# main_board.net
KiCad netlist of a schematic drawn in EAGLE
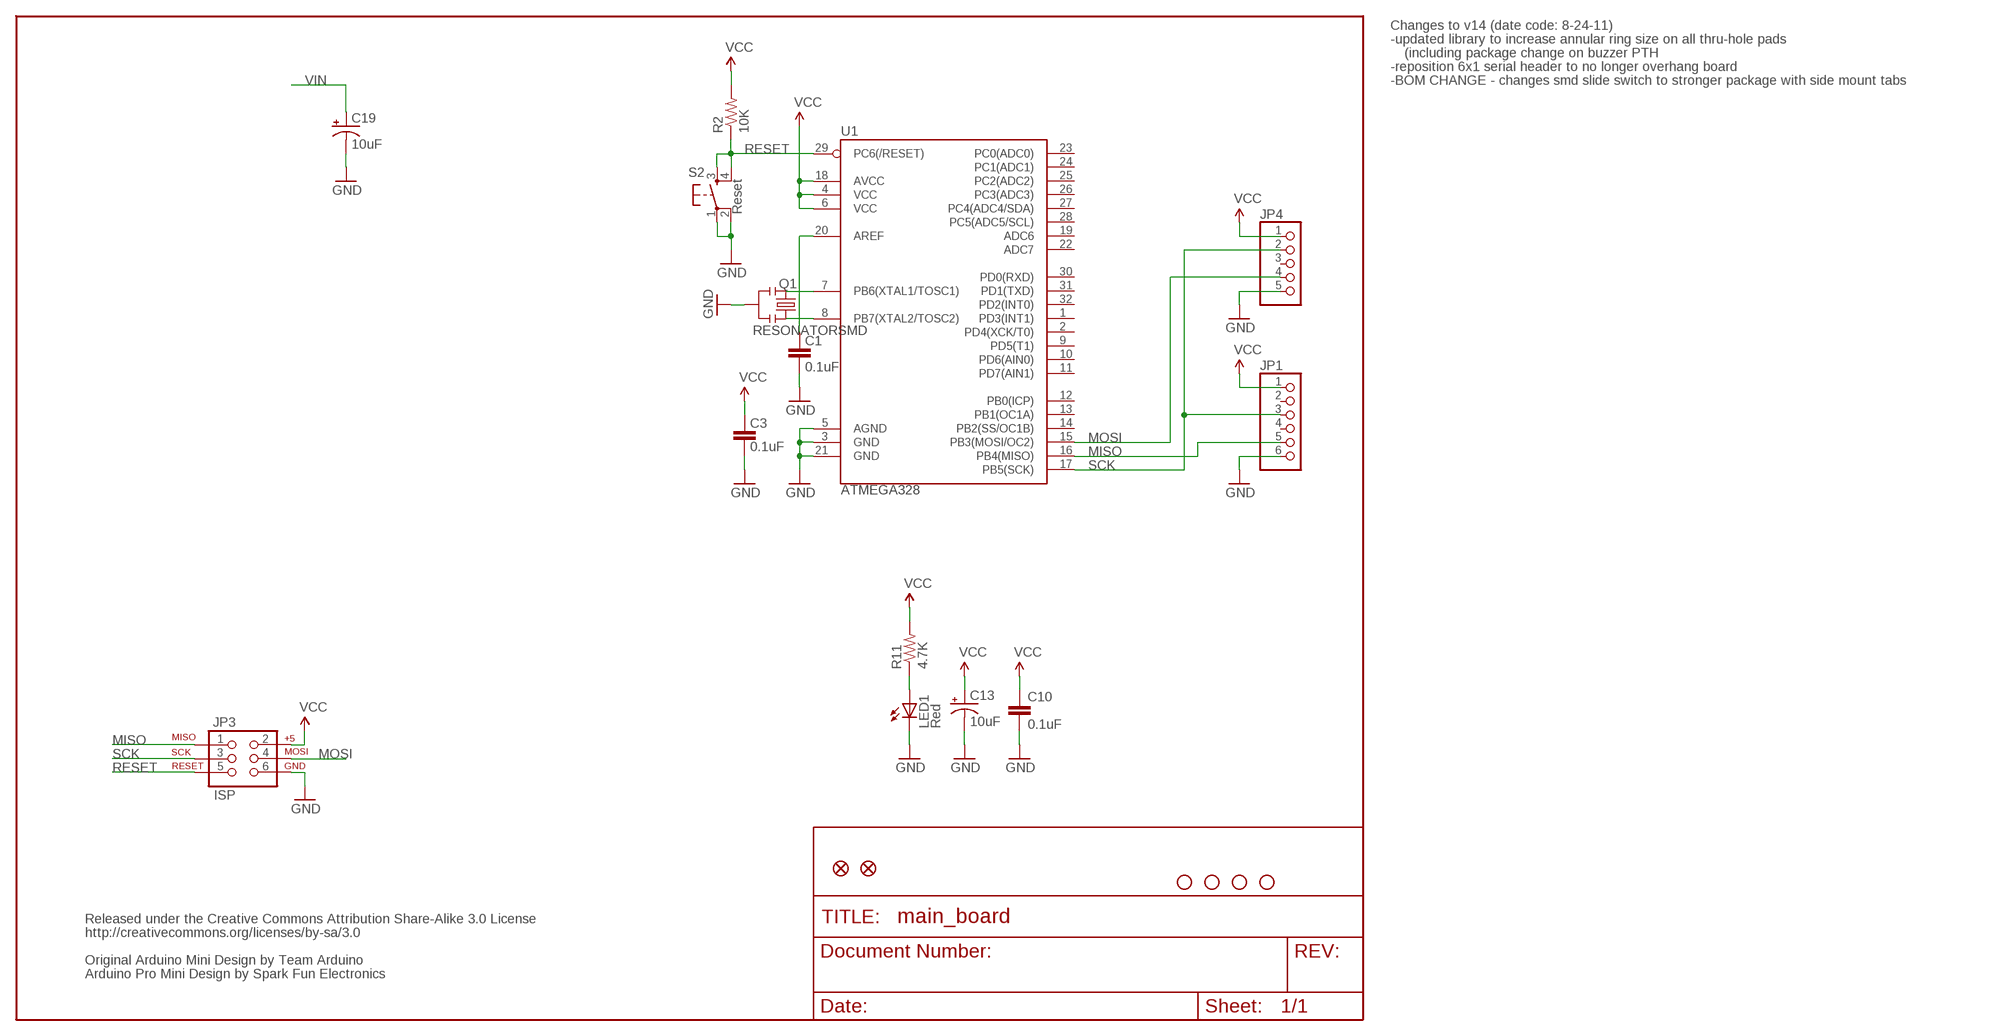
[diagram p0: schematic, sheet 1]

(export (version "E")
  (design (tool "Eeschema 10.0.6"))
  (components
    (comp (ref "C1")
      (value "0.1uF")
      (footprint "eagle-import:0402-CAP")
      (libsource (lib "eagle-import") (part "CAP0402-CAP"))
    )
    (comp (ref "C3")
      (value "0.1uF")
      (footprint "eagle-import:0402-CAP")
      (libsource (lib "eagle-import") (part "CAP0402-CAP"))
    )
    (comp (ref "C10")
      (value "0.1uF")
      (footprint "eagle-import:0402-CAP")
      (libsource (lib "eagle-import") (part "CAP0402-CAP"))
    )
    (comp (ref "C13")
      (value "10uF")
      (footprint "eagle-import:EIA3216")
      (libsource (lib "eagle-import") (part "CAP_POL1206"))
    )
    (comp (ref "C19")
      (value "10uF")
      (footprint "eagle-import:EIA3216")
      (libsource (lib "eagle-import") (part "CAP_POL1206"))
    )
    (comp (ref "JP1")
      (value "PINHD-1X6")
      (footprint "eagle-import:1X06")
      (libsource (lib "eagle-import") (part "PINHD-1X6"))
    )
    (comp (ref "JP2")
      (value "FIDUCIAL1X2.5")
      (footprint "eagle-import:FIDUCIAL-1X2.5")
      (libsource (lib "eagle-import") (part "FIDUCIAL1X2.5"))
    )
    (comp (ref "JP3")
      (value "ISP")
      (footprint "eagle-import:2X3")
      (libsource (lib "eagle-import") (part "AVR_SPI_PRG_6PTH"))
    )
    (comp (ref "JP4")
      (value "PINHD-1X5")
      (footprint "eagle-import:1X05")
      (libsource (lib "eagle-import") (part "PINHD-1X5"))
    )
    (comp (ref "JP5")
      (value "FIDUCIAL1X2.5")
      (footprint "eagle-import:FIDUCIAL-1X2.5")
      (libsource (lib "eagle-import") (part "FIDUCIAL1X2.5"))
    )
    (comp (ref "LED1")
      (value "Red")
      (footprint "eagle-import:LED-0603")
      (libsource (lib "eagle-import") (part "LED0603"))
    )
    (comp (ref "Q1")
      (value "RESONATORSMD")
      (footprint "eagle-import:RESONATOR-SMD")
      (libsource (lib "eagle-import") (part "RESONATORSMD"))
    )
    (comp (ref "R2")
      (value "10K")
      (footprint "eagle-import:0402-RES")
      (libsource (lib "eagle-import") (part "RESISTOR0402-RES"))
    )
    (comp (ref "R11")
      (value "4.7K")
      (footprint "eagle-import:0402-RES")
      (libsource (lib "eagle-import") (part "RESISTOR0402-RES"))
    )
    (comp (ref "S2")
      (value "Reset")
      (footprint "eagle-import:TACTILE_SWITCH_SMD")
      (libsource (lib "eagle-import") (part "TAC_SWITCHSMD"))
    )
    (comp (ref "U$1")
      (value "STAND-OFF")
      (footprint "eagle-import:STAND-OFF")
      (libsource (lib "eagle-import") (part "STAND-OFF"))
    )
    (comp (ref "U$3")
      (value "STAND-OFF")
      (footprint "eagle-import:STAND-OFF")
      (libsource (lib "eagle-import") (part "STAND-OFF"))
    )
    (comp (ref "U$9")
      (value "STAND-OFF")
      (footprint "eagle-import:STAND-OFF")
      (libsource (lib "eagle-import") (part "STAND-OFF"))
    )
    (comp (ref "U$10")
      (value "STAND-OFF")
      (footprint "eagle-import:STAND-OFF")
      (libsource (lib "eagle-import") (part "STAND-OFF"))
    )
    (comp (ref "U1")
      (value "ATMEGA328")
      (footprint "eagle-import:TQFP32-08")
      (libsource (lib "eagle-import") (part "ATMEGA168"))
    )
  )
  (nets
    (net (code "1") (name "/MISO") (class "Default")
      (node (ref "JP1") (pin "5") (pinfunction "5_5") (pintype "passive"))
      (node (ref "JP3") (pin "1") (pinfunction "1_1") (pintype "passive"))
      (node (ref "U1") (pin "16") (pinfunction "PB4(MISO)_16") (pintype "bidirectional"))
    )
    (net (code "2") (name "/MOSI") (class "Default")
      (node (ref "JP3") (pin "4") (pinfunction "4_4") (pintype "passive"))
      (node (ref "JP4") (pin "4") (pinfunction "4_4") (pintype "passive"))
      (node (ref "U1") (pin "15") (pinfunction "PB3(MOSI/OC2)_15") (pintype "bidirectional"))
    )
    (net (code "3") (name "/RESET") (class "Default")
      (node (ref "JP3") (pin "5") (pinfunction "5_5") (pintype "passive"))
      (node (ref "R2") (pin "1") (pinfunction "1_1") (pintype "passive"))
      (node (ref "S2") (pin "3") (pinfunction "3_3") (pintype "passive"))
      (node (ref "S2") (pin "4") (pinfunction "4_4") (pintype "passive"))
      (node (ref "U1") (pin "29") (pinfunction "PC6(/RESET)_29") (pintype "bidirectional"))
    )
    (net (code "4") (name "/SCK") (class "Default")
      (node (ref "JP1") (pin "3") (pinfunction "3_3") (pintype "passive"))
      (node (ref "JP3") (pin "3") (pinfunction "3_3") (pintype "passive"))
      (node (ref "JP4") (pin "2") (pinfunction "2_2") (pintype "passive"))
      (node (ref "U1") (pin "17") (pinfunction "PB5(SCK)_17") (pintype "bidirectional"))
    )
    (net (code "5") (name "/VIN") (class "Default")
      (node (ref "C19") (pin "A") (pinfunction "+_A") (pintype "passive"))
    )
    (net (code "6") (name "GND") (class "Default")
      (node (ref "C1") (pin "1") (pinfunction "1_1") (pintype "passive"))
      (node (ref "C10") (pin "2") (pinfunction "2_2") (pintype "passive"))
      (node (ref "C13") (pin "C") (pinfunction "-_C") (pintype "passive"))
      (node (ref "C19") (pin "C") (pinfunction "-_C") (pintype "passive"))
      (node (ref "C3") (pin "1") (pinfunction "1_1") (pintype "passive"))
      (node (ref "JP1") (pin "6") (pinfunction "6_6") (pintype "passive"))
      (node (ref "JP3") (pin "6") (pinfunction "6_6") (pintype "passive"))
      (node (ref "JP4") (pin "5") (pinfunction "5_5") (pintype "passive"))
      (node (ref "LED1") (pin "C") (pinfunction "C_C") (pintype "passive"))
      (node (ref "Q1") (pin "2") (pinfunction "2_2") (pintype "passive"))
      (node (ref "S2") (pin "1") (pinfunction "1_1") (pintype "passive"))
      (node (ref "S2") (pin "2") (pinfunction "2_2") (pintype "passive"))
      (node (ref "U1") (pin "21") (pinfunction "GND_21") (pintype "bidirectional"))
      (node (ref "U1") (pin "3") (pinfunction "GND_3") (pintype "bidirectional"))
      (node (ref "U1") (pin "5") (pinfunction "AGND_5") (pintype "bidirectional"))
    )
    (net (code "7") (name "Net-(LED1-PadA)") (class "Default")
      (node (ref "LED1") (pin "A") (pinfunction "A_A") (pintype "passive"))
      (node (ref "R11") (pin "1") (pinfunction "1_1") (pintype "passive"))
    )
    (net (code "8") (name "Net-(U1-AREF)") (class "Default")
      (node (ref "C1") (pin "2") (pinfunction "2_2") (pintype "passive"))
      (node (ref "U1") (pin "20") (pinfunction "AREF_20") (pintype "bidirectional"))
    )
    (net (code "9") (name "Net-(U1-PB6(XTAL1{slash}TOSC1))") (class "Default")
      (node (ref "Q1") (pin "3") (pinfunction "3_3") (pintype "passive"))
      (node (ref "U1") (pin "7") (pinfunction "PB6(XTAL1/TOSC1)_7") (pintype "bidirectional"))
    )
    (net (code "10") (name "Net-(U1-PB7(XTAL2{slash}TOSC2))") (class "Default")
      (node (ref "Q1") (pin "1") (pinfunction "1_1") (pintype "passive"))
      (node (ref "U1") (pin "8") (pinfunction "PB7(XTAL2/TOSC2)_8") (pintype "bidirectional"))
    )
    (net (code "11") (name "VCC") (class "Default")
      (node (ref "C10") (pin "1") (pinfunction "1_1") (pintype "passive"))
      (node (ref "C13") (pin "A") (pinfunction "+_A") (pintype "passive"))
      (node (ref "C3") (pin "2") (pinfunction "2_2") (pintype "passive"))
      (node (ref "JP1") (pin "1") (pinfunction "1_1") (pintype "passive"))
      (node (ref "JP3") (pin "2") (pinfunction "2_2") (pintype "passive"))
      (node (ref "JP4") (pin "1") (pinfunction "1_1") (pintype "passive"))
      (node (ref "R11") (pin "2") (pinfunction "2_2") (pintype "passive"))
      (node (ref "R2") (pin "2") (pinfunction "2_2") (pintype "passive"))
      (node (ref "U1") (pin "18") (pinfunction "AVCC_18") (pintype "bidirectional"))
      (node (ref "U1") (pin "4") (pinfunction "VCC_4") (pintype "bidirectional"))
      (node (ref "U1") (pin "6") (pinfunction "VCC_6") (pintype "bidirectional"))
    )
    (net (code "12") (name "unconnected-(JP1-Pad2)") (class "Default")
      (node (ref "JP1") (pin "2") (pinfunction "2_2") (pintype "passive"))
    )
    (net (code "13") (name "unconnected-(JP1-Pad4)") (class "Default")
      (node (ref "JP1") (pin "4") (pinfunction "4_4") (pintype "passive"))
    )
    (net (code "14") (name "unconnected-(JP4-Pad3)") (class "Default")
      (node (ref "JP4") (pin "3") (pinfunction "3_3") (pintype "passive"))
    )
    (net (code "15") (name "unconnected-(U1-ADC6-Pad19)") (class "Default")
      (node (ref "U1") (pin "19") (pinfunction "ADC6_19") (pintype "bidirectional"))
    )
    (net (code "16") (name "unconnected-(U1-ADC7-Pad22)") (class "Default")
      (node (ref "U1") (pin "22") (pinfunction "ADC7_22") (pintype "bidirectional"))
    )
    (net (code "17") (name "unconnected-(U1-PB0(ICP)-Pad12)") (class "Default")
      (node (ref "U1") (pin "12") (pinfunction "PB0(ICP)_12") (pintype "bidirectional"))
    )
    (net (code "18") (name "unconnected-(U1-PB1(OC1A)-Pad13)") (class "Default")
      (node (ref "U1") (pin "13") (pinfunction "PB1(OC1A)_13") (pintype "bidirectional"))
    )
    (net (code "19") (name "unconnected-(U1-PB2(SS{slash}OC1B)-Pad14)") (class "Default")
      (node (ref "U1") (pin "14") (pinfunction "PB2(SS/OC1B)_14") (pintype "bidirectional"))
    )
    (net (code "20") (name "unconnected-(U1-PC0(ADC0)-Pad23)") (class "Default")
      (node (ref "U1") (pin "23") (pinfunction "PC0(ADC0)_23") (pintype "bidirectional"))
    )
    (net (code "21") (name "unconnected-(U1-PC1(ADC1)-Pad24)") (class "Default")
      (node (ref "U1") (pin "24") (pinfunction "PC1(ADC1)_24") (pintype "bidirectional"))
    )
    (net (code "22") (name "unconnected-(U1-PC2(ADC2)-Pad25)") (class "Default")
      (node (ref "U1") (pin "25") (pinfunction "PC2(ADC2)_25") (pintype "bidirectional"))
    )
    (net (code "23") (name "unconnected-(U1-PC3(ADC3)-Pad26)") (class "Default")
      (node (ref "U1") (pin "26") (pinfunction "PC3(ADC3)_26") (pintype "bidirectional"))
    )
    (net (code "24") (name "unconnected-(U1-PC4(ADC4{slash}SDA)-Pad27)") (class "Default")
      (node (ref "U1") (pin "27") (pinfunction "PC4(ADC4/SDA)_27") (pintype "bidirectional"))
    )
    (net (code "25") (name "unconnected-(U1-PC5(ADC5{slash}SCL)-Pad28)") (class "Default")
      (node (ref "U1") (pin "28") (pinfunction "PC5(ADC5/SCL)_28") (pintype "bidirectional"))
    )
    (net (code "26") (name "unconnected-(U1-PD0(RXD)-Pad30)") (class "Default")
      (node (ref "U1") (pin "30") (pinfunction "PD0(RXD)_30") (pintype "bidirectional"))
    )
    (net (code "27") (name "unconnected-(U1-PD1(TXD)-Pad31)") (class "Default")
      (node (ref "U1") (pin "31") (pinfunction "PD1(TXD)_31") (pintype "bidirectional"))
    )
    (net (code "28") (name "unconnected-(U1-PD2(INT0)-Pad32)") (class "Default")
      (node (ref "U1") (pin "32") (pinfunction "PD2(INT0)_32") (pintype "bidirectional"))
    )
    (net (code "29") (name "unconnected-(U1-PD3(INT1)-Pad1)") (class "Default")
      (node (ref "U1") (pin "1") (pinfunction "PD3(INT1)_1") (pintype "bidirectional"))
    )
    (net (code "30") (name "unconnected-(U1-PD4(XCK{slash}T0)-Pad2)") (class "Default")
      (node (ref "U1") (pin "2") (pinfunction "PD4(XCK/T0)_2") (pintype "bidirectional"))
    )
    (net (code "31") (name "unconnected-(U1-PD5(T1)-Pad9)") (class "Default")
      (node (ref "U1") (pin "9") (pinfunction "PD5(T1)_9") (pintype "bidirectional"))
    )
    (net (code "32") (name "unconnected-(U1-PD6(AIN0)-Pad10)") (class "Default")
      (node (ref "U1") (pin "10") (pinfunction "PD6(AIN0)_10") (pintype "bidirectional"))
    )
    (net (code "33") (name "unconnected-(U1-PD7(AIN1)-Pad11)") (class "Default")
      (node (ref "U1") (pin "11") (pinfunction "PD7(AIN1)_11") (pintype "bidirectional"))
    )
  )
)
